# CMOD_A7.net
KiCad netlist of a schematic drawn in Altium Designer
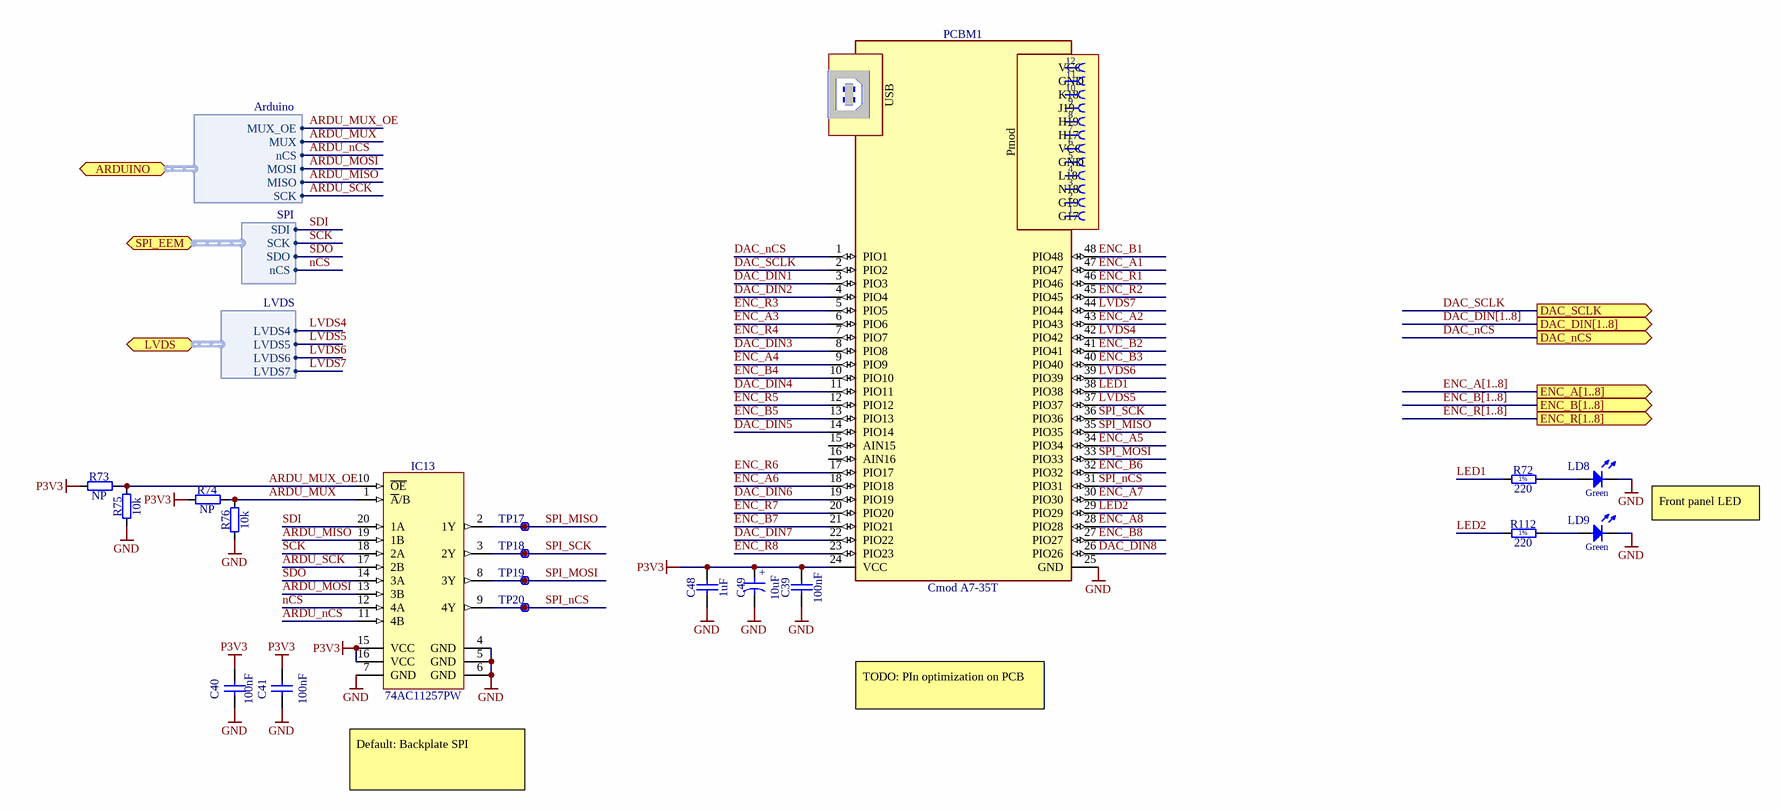
[diagram p0: CMOD_A7.SchDoc]

(export (version "E")
  (design (tool "Eeschema 10.0.6"))
  (components
    (comp (ref "C39")
      (value "100nF")
      (footprint "CAPC1005X55N")
      (description "Non-polarised capacitor")
      (fields
        (field (name "PART NUMBER") "CC0402_100NF_16V_10%_X5R")
        (field (name "VOLTAGE") "16V")
        (field (name "AUTHOR") "CERN DEM JLC")
      )
      (libsource (lib "Capacitors") (part "Capacitor - non polarized"))
    )
    (comp (ref "C40")
      (value "100nF")
      (footprint "CAPC1005X55N")
      (description "Non-polarised capacitor")
      (fields
        (field (name "PART NUMBER") "CC0402_100NF_16V_10%_X5R")
        (field (name "VOLTAGE") "16V")
        (field (name "AUTHOR") "CERN DEM JLC")
      )
      (libsource (lib "Capacitors") (part "Capacitor - non polarized"))
    )
    (comp (ref "C41")
      (value "100nF")
      (footprint "CAPC1005X55N")
      (description "Non-polarised capacitor")
      (fields
        (field (name "PART NUMBER") "CC0402_100NF_16V_10%_X5R")
        (field (name "VOLTAGE") "16V")
        (field (name "AUTHOR") "CERN DEM JLC")
      )
      (libsource (lib "Capacitors") (part "Capacitor - non polarized"))
    )
    (comp (ref "C48")
      (value "1uF")
      (footprint "CAPC1608X87N")
      (description "Non-polarised capacitor")
      (fields
        (field (name "PART NUMBER") "CC0603_1UF_25V_10%_X7R")
        (field (name "VOLTAGE") "25V")
        (field (name "AUTHOR") "CERN DEM JLC")
      )
      (libsource (lib "Capacitors") (part "Capacitor - non polarized"))
    )
    (comp (ref "C49")
      (value "10uF")
      (footprint "CAPMP3216X180N")
      (description "Polarised capacitor")
      (fields
        (field (name "PART NUMBER") "CTE3216-18_10UF_16V_20%_AVX_TCJ")
        (field (name "VOLTAGE") "16V")
        (field (name "AUTHOR") "CERN DEM JLC")
      )
      (libsource (lib "Capacitors") (part "Capacitor - polarized"))
    )
    (comp (ref "IC13")
      (value "74AC11257PW")
      (footprint "SOP65P640X120-20N")
      (description "Quadruple 2-Line to 1-Line Data Selector/Multiplexer With 3-State Outputs")
      (fields (field (name "MANUFACTURER") "TEXAS INSTRUMENTS") (field (name "AUTHOR") "CERN DEM JLC"))
      (libsource (lib "ICs And Semiconductors") (part "7411257"))
    )
    (comp (ref "LD8")
      (value "Green")
      (footprint "LED_DIALIGHT_555-230")
      (description "LED Green 1C 2A")
      (fields
        (field (name "PART NUMBER") "LED_DIALIGHT_555-2301F")
        (field (name "MANUFACTURER") "DIALIGHT")
        (field (name "AUTHOR") "CERN DEM JMW")
      )
      (libsource (lib "ICs And Semiconductors") (part "LED Green 1C 2A"))
    )
    (comp (ref "LD9")
      (value "Green")
      (footprint "LED_DIALIGHT_555-230")
      (description "LED Green 1C 2A")
      (fields
        (field (name "PART NUMBER") "LED_DIALIGHT_555-2301F")
        (field (name "MANUFACTURER") "DIALIGHT")
        (field (name "AUTHOR") "CERN DEM JMW")
      )
      (libsource (lib "ICs And Semiconductors") (part "LED Green 1C 2A"))
    )
    (comp (ref "PCBM1")
      (value "Cmod A7-35T")
      (footprint "PCBM_DIGILENT_CMODA7")
      (description "Breadboardable Artix-7 FPGA Module")
      (fields
        (field (name "PART NUMBER") "PCBM_DIGILENT_CMOD A7-35T")
        (field (name "MANUFACTURER") "DIGILENT")
        (field (name "AUTHOR") "CERN DEM BC")
      )
      (libsource (lib "ICs And Semiconductors") (part "PCBM_DIGILENT_CMODA7"))
    )
    (comp (ref "R72")
      (value "220")
      (footprint "RESC1608X55N")
      (description "Resistor - 1%")
      (fields
        (field (name "PART NUMBER") "R0603_220R_1%_0.1W_100PPM")
        (field (name "POWER") "0.1W")
        (field (name "AUTHOR") "CERN DEM JLC")
      )
      (libsource (lib "") (part "Resistor - 1%_1"))
    )
    (comp (ref "R73")
      (value "NP")
      (footprint "RESC1005X40N")
      (description "Resistor - 1%")
      (fields
        (field (name "PART NUMBER") "R0402_10K_1%_0.0625W_100PPM")
        (field (name "POWER") "0.0625W")
        (field (name "AUTHOR") "CERN DEM JLC")
      )
      (libsource (lib "Resistors") (part "Resistor - 1%"))
    )
    (comp (ref "R74")
      (value "NP")
      (footprint "RESC1005X40N")
      (description "Resistor - 1%")
      (fields
        (field (name "PART NUMBER") "R0402_10K_1%_0.0625W_100PPM")
        (field (name "POWER") "0.0625W")
        (field (name "AUTHOR") "CERN DEM JLC")
      )
      (libsource (lib "Resistors") (part "Resistor - 1%"))
    )
    (comp (ref "R75")
      (value "10k")
      (footprint "RESC1005X40N")
      (description "Resistor - 1%")
      (fields
        (field (name "PART NUMBER") "R0402_10K_1%_0.0625W_100PPM")
        (field (name "POWER") "0.0625W")
        (field (name "AUTHOR") "CERN DEM JLC")
      )
      (libsource (lib "Resistors") (part "Resistor - 1%"))
    )
    (comp (ref "R76")
      (value "10k")
      (footprint "RESC1005X40N")
      (description "Resistor - 1%")
      (fields
        (field (name "PART NUMBER") "R0402_10K_1%_0.0625W_100PPM")
        (field (name "POWER") "0.0625W")
        (field (name "AUTHOR") "CERN DEM JLC")
      )
      (libsource (lib "Resistors") (part "Resistor - 1%"))
    )
    (comp (ref "R112")
      (value "220")
      (footprint "RESC1608X55N")
      (description "Resistor - 1%")
      (fields
        (field (name "PART NUMBER") "R0603_220R_1%_0.1W_100PPM")
        (field (name "POWER") "0.1W")
        (field (name "AUTHOR") "CERN DEM JLC")
      )
      (libsource (lib "") (part "Resistor - 1%_1"))
    )
    (comp (ref "TP17")
      (value "Plated Hole")
      (footprint "c130h60")
      (description "Single Terminal Socket")
      (fields (field (name "PART NUMBER") "PLATED_HOLE0.6_PAD1.3") (field (name "AUTHOR") "CERN DEM MR"))
      (libsource (lib "Eletro-mechanical") (part "Single Terminal Socket"))
    )
    (comp (ref "TP18")
      (value "Plated Hole")
      (footprint "c130h60")
      (description "Single Terminal Socket")
      (fields (field (name "PART NUMBER") "PLATED_HOLE0.6_PAD1.3") (field (name "AUTHOR") "CERN DEM MR"))
      (libsource (lib "Eletro-mechanical") (part "Single Terminal Socket"))
    )
    (comp (ref "TP19")
      (value "Plated Hole")
      (footprint "c130h60")
      (description "Single Terminal Socket")
      (fields (field (name "PART NUMBER") "PLATED_HOLE0.6_PAD1.3") (field (name "AUTHOR") "CERN DEM MR"))
      (libsource (lib "Eletro-mechanical") (part "Single Terminal Socket"))
    )
    (comp (ref "TP20")
      (value "Plated Hole")
      (footprint "c130h60")
      (description "Single Terminal Socket")
      (fields (field (name "PART NUMBER") "PLATED_HOLE0.6_PAD1.3") (field (name "AUTHOR") "CERN DEM MR"))
      (libsource (lib "Eletro-mechanical") (part "Single Terminal Socket"))
    )
  )
  (nets
    (net (code "4") (name "/ARDU_MISO") (class "Default")
      (node (ref "IC13") (pin "19") (pinfunction "1B_19") (pintype "input"))
    )
    (net (code "5") (name "/ARDU_MOSI") (class "Default")
      (node (ref "IC13") (pin "13") (pinfunction "3B_13") (pintype "input"))
    )
    (net (code "6") (name "/ARDU_MUX") (class "Default")
      (node (ref "IC13") (pin "1") (pinfunction "~{A}/B_1") (pintype "input"))
      (node (ref "R74") (pin "2") (pinfunction "2_2") (pintype "passive"))
      (node (ref "R76") (pin "2") (pinfunction "2_2") (pintype "passive"))
    )
    (net (code "7") (name "/ARDU_MUX_OE") (class "Default")
      (node (ref "IC13") (pin "10") (pinfunction "~{OE}_10") (pintype "input"))
      (node (ref "R73") (pin "2") (pinfunction "2_2") (pintype "passive"))
      (node (ref "R75") (pin "2") (pinfunction "2_2") (pintype "passive"))
    )
    (net (code "8") (name "/ARDU_SCK") (class "Default")
      (node (ref "IC13") (pin "17") (pinfunction "2B_17") (pintype "input"))
    )
    (net (code "9") (name "/ARDU_nCS") (class "Default")
      (node (ref "IC13") (pin "11") (pinfunction "4B_11") (pintype "input"))
    )
    (net (code "10") (name "/DAC_DIN1") (class "Default")
      (node (ref "PCBM1") (pin "3") (pinfunction "PIO3_3") (pintype "bidirectional"))
    )
    (net (code "11") (name "/DAC_DIN2") (class "Default")
      (node (ref "PCBM1") (pin "4") (pinfunction "PIO4_4") (pintype "bidirectional"))
    )
    (net (code "12") (name "/DAC_DIN3") (class "Default")
      (node (ref "PCBM1") (pin "8") (pinfunction "PIO8_8") (pintype "bidirectional"))
    )
    (net (code "13") (name "/DAC_DIN4") (class "Default")
      (node (ref "PCBM1") (pin "11") (pinfunction "PIO11_11") (pintype "bidirectional"))
    )
    (net (code "14") (name "/DAC_DIN5") (class "Default")
      (node (ref "PCBM1") (pin "14") (pinfunction "PIO14_14") (pintype "bidirectional"))
    )
    (net (code "15") (name "/DAC_DIN6") (class "Default")
      (node (ref "PCBM1") (pin "19") (pinfunction "PIO19_19") (pintype "bidirectional"))
    )
    (net (code "16") (name "/DAC_DIN7") (class "Default")
      (node (ref "PCBM1") (pin "22") (pinfunction "PIO22_22") (pintype "bidirectional"))
    )
    (net (code "17") (name "/DAC_DIN8") (class "Default")
      (node (ref "PCBM1") (pin "26") (pinfunction "PIO26_26") (pintype "bidirectional"))
    )
    (net (code "19") (name "/DAC_SCLK") (class "Default")
      (node (ref "PCBM1") (pin "2") (pinfunction "PIO2_2") (pintype "bidirectional"))
    )
    (net (code "20") (name "/DAC_nCS") (class "Default")
      (node (ref "PCBM1") (pin "1") (pinfunction "PIO1_1") (pintype "bidirectional"))
    )
    (net (code "21") (name "/ENC_A1") (class "Default")
      (node (ref "PCBM1") (pin "47") (pinfunction "PIO47_47") (pintype "bidirectional"))
    )
    (net (code "22") (name "/ENC_A2") (class "Default")
      (node (ref "PCBM1") (pin "43") (pinfunction "PIO43_43") (pintype "bidirectional"))
    )
    (net (code "23") (name "/ENC_A3") (class "Default")
      (node (ref "PCBM1") (pin "6") (pinfunction "PIO6_6") (pintype "bidirectional"))
    )
    (net (code "24") (name "/ENC_A4") (class "Default")
      (node (ref "PCBM1") (pin "9") (pinfunction "PIO9_9") (pintype "bidirectional"))
    )
    (net (code "25") (name "/ENC_A5") (class "Default")
      (node (ref "PCBM1") (pin "34") (pinfunction "PIO34_34") (pintype "bidirectional"))
    )
    (net (code "26") (name "/ENC_A6") (class "Default")
      (node (ref "PCBM1") (pin "18") (pinfunction "PIO18_18") (pintype "bidirectional"))
    )
    (net (code "27") (name "/ENC_A7") (class "Default")
      (node (ref "PCBM1") (pin "30") (pinfunction "PIO30_30") (pintype "bidirectional"))
    )
    (net (code "28") (name "/ENC_A8") (class "Default")
      (node (ref "PCBM1") (pin "28") (pinfunction "PIO28_28") (pintype "bidirectional"))
    )
    (net (code "30") (name "/ENC_B1") (class "Default")
      (node (ref "PCBM1") (pin "48") (pinfunction "PIO48_48") (pintype "bidirectional"))
    )
    (net (code "31") (name "/ENC_B2") (class "Default")
      (node (ref "PCBM1") (pin "41") (pinfunction "PIO41_41") (pintype "bidirectional"))
    )
    (net (code "32") (name "/ENC_B3") (class "Default")
      (node (ref "PCBM1") (pin "40") (pinfunction "PIO40_40") (pintype "bidirectional"))
    )
    (net (code "33") (name "/ENC_B4") (class "Default")
      (node (ref "PCBM1") (pin "10") (pinfunction "PIO10_10") (pintype "bidirectional"))
    )
    (net (code "34") (name "/ENC_B5") (class "Default")
      (node (ref "PCBM1") (pin "13") (pinfunction "PIO13_13") (pintype "bidirectional"))
    )
    (net (code "35") (name "/ENC_B6") (class "Default")
      (node (ref "PCBM1") (pin "32") (pinfunction "PIO32_32") (pintype "bidirectional"))
    )
    (net (code "36") (name "/ENC_B7") (class "Default")
      (node (ref "PCBM1") (pin "21") (pinfunction "PIO21_21") (pintype "bidirectional"))
    )
    (net (code "37") (name "/ENC_B8") (class "Default")
      (node (ref "PCBM1") (pin "27") (pinfunction "PIO27_27") (pintype "bidirectional"))
    )
    (net (code "39") (name "/ENC_R1") (class "Default")
      (node (ref "PCBM1") (pin "46") (pinfunction "PIO46_46") (pintype "bidirectional"))
    )
    (net (code "40") (name "/ENC_R2") (class "Default")
      (node (ref "PCBM1") (pin "45") (pinfunction "PIO45_45") (pintype "bidirectional"))
    )
    (net (code "41") (name "/ENC_R3") (class "Default")
      (node (ref "PCBM1") (pin "5") (pinfunction "PIO5_5") (pintype "bidirectional"))
    )
    (net (code "42") (name "/ENC_R4") (class "Default")
      (node (ref "PCBM1") (pin "7") (pinfunction "PIO7_7") (pintype "bidirectional"))
    )
    (net (code "43") (name "/ENC_R5") (class "Default")
      (node (ref "PCBM1") (pin "12") (pinfunction "PIO12_12") (pintype "bidirectional"))
    )
    (net (code "44") (name "/ENC_R6") (class "Default")
      (node (ref "PCBM1") (pin "17") (pinfunction "PIO17_17") (pintype "bidirectional"))
    )
    (net (code "45") (name "/ENC_R7") (class "Default")
      (node (ref "PCBM1") (pin "20") (pinfunction "PIO20_20") (pintype "bidirectional"))
    )
    (net (code "46") (name "/ENC_R8") (class "Default")
      (node (ref "PCBM1") (pin "23") (pinfunction "PIO23_23") (pintype "bidirectional"))
    )
    (net (code "48") (name "/LED1") (class "Default")
      (node (ref "PCBM1") (pin "38") (pinfunction "PIO38_38") (pintype "bidirectional"))
      (node (ref "R72") (pin "1") (pinfunction "1_1") (pintype "passive"))
    )
    (net (code "49") (name "/LED2") (class "Default")
      (node (ref "PCBM1") (pin "29") (pinfunction "PIO29_29") (pintype "bidirectional"))
      (node (ref "R112") (pin "1") (pinfunction "1_1") (pintype "passive"))
    )
    (net (code "50") (name "/LVDS4") (class "Default")
      (node (ref "PCBM1") (pin "42") (pinfunction "PIO42_42") (pintype "bidirectional"))
    )
    (net (code "51") (name "/LVDS5") (class "Default")
      (node (ref "PCBM1") (pin "37") (pinfunction "PIO37_37") (pintype "bidirectional"))
    )
    (net (code "52") (name "/LVDS6") (class "Default")
      (node (ref "PCBM1") (pin "39") (pinfunction "PIO39_39") (pintype "bidirectional"))
    )
    (net (code "53") (name "/LVDS7") (class "Default")
      (node (ref "PCBM1") (pin "44") (pinfunction "PIO44_44") (pintype "bidirectional"))
    )
    (net (code "54") (name "/SCK") (class "Default")
      (node (ref "IC13") (pin "18") (pinfunction "2A_18") (pintype "input"))
    )
    (net (code "55") (name "/SDI") (class "Default")
      (node (ref "IC13") (pin "20") (pinfunction "1A_20") (pintype "input"))
    )
    (net (code "56") (name "/SDO") (class "Default")
      (node (ref "IC13") (pin "14") (pinfunction "3A_14") (pintype "input"))
    )
    (net (code "57") (name "/SPI_MISO") (class "Default")
      (node (ref "IC13") (pin "2") (pinfunction "1Y_2") (pintype "output"))
      (node (ref "PCBM1") (pin "35") (pinfunction "PIO35_35") (pintype "bidirectional"))
      (node (ref "TP17") (pin "1") (pinfunction "1_1") (pintype "bidirectional"))
    )
    (net (code "58") (name "/SPI_MOSI") (class "Default")
      (node (ref "IC13") (pin "8") (pinfunction "3Y_8") (pintype "output"))
      (node (ref "PCBM1") (pin "33") (pinfunction "PIO33_33") (pintype "bidirectional"))
      (node (ref "TP19") (pin "1") (pinfunction "1_1") (pintype "bidirectional"))
    )
    (net (code "59") (name "/SPI_SCK") (class "Default")
      (node (ref "IC13") (pin "3") (pinfunction "2Y_3") (pintype "output"))
      (node (ref "PCBM1") (pin "36") (pinfunction "PIO36_36") (pintype "bidirectional"))
      (node (ref "TP18") (pin "1") (pinfunction "1_1") (pintype "bidirectional"))
    )
    (net (code "60") (name "/SPI_nCS") (class "Default")
      (node (ref "IC13") (pin "9") (pinfunction "4Y_9") (pintype "output"))
      (node (ref "PCBM1") (pin "31") (pinfunction "PIO31_31") (pintype "bidirectional"))
      (node (ref "TP20") (pin "1") (pinfunction "1_1") (pintype "bidirectional"))
    )
    (net (code "61") (name "/nCS") (class "Default")
      (node (ref "IC13") (pin "12") (pinfunction "4A_12") (pintype "input"))
    )
    (net (code "65") (name "GND") (class "Default")
      (node (ref "C39") (pin "1") (pinfunction "1_1") (pintype "passive"))
      (node (ref "C40") (pin "1") (pinfunction "1_1") (pintype "passive"))
      (node (ref "C41") (pin "1") (pinfunction "1_1") (pintype "passive"))
      (node (ref "C48") (pin "1") (pinfunction "1_1") (pintype "passive"))
      (node (ref "C49") (pin "2") (pinfunction "2_2") (pintype "passive"))
      (node (ref "IC13") (pin "4") (pinfunction "GND_4") (pintype "power_in"))
      (node (ref "IC13") (pin "5") (pinfunction "GND_5") (pintype "power_in"))
      (node (ref "IC13") (pin "6") (pinfunction "GND_6") (pintype "power_in"))
      (node (ref "IC13") (pin "7") (pinfunction "GND_7") (pintype "power_in"))
      (node (ref "LD8") (pin "1") (pinfunction "C_1") (pintype "passive"))
      (node (ref "LD9") (pin "1") (pinfunction "C_1") (pintype "passive"))
      (node (ref "PCBM1") (pin "25") (pinfunction "GND_25") (pintype "power_in"))
      (node (ref "R75") (pin "1") (pinfunction "1_1") (pintype "passive"))
      (node (ref "R76") (pin "1") (pinfunction "1_1") (pintype "passive"))
    )
    (net (code "66") (name "Net-(LD8-A)") (class "Default")
      (node (ref "LD8") (pin "2") (pinfunction "A_2") (pintype "passive"))
      (node (ref "R72") (pin "2") (pinfunction "2_2") (pintype "passive"))
    )
    (net (code "67") (name "Net-(LD9-A)") (class "Default")
      (node (ref "LD9") (pin "2") (pinfunction "A_2") (pintype "passive"))
      (node (ref "R112") (pin "2") (pinfunction "2_2") (pintype "passive"))
    )
    (net (code "68") (name "P3V3") (class "Default")
      (node (ref "C39") (pin "2") (pinfunction "2_2") (pintype "passive"))
      (node (ref "C40") (pin "2") (pinfunction "2_2") (pintype "passive"))
      (node (ref "C41") (pin "2") (pinfunction "2_2") (pintype "passive"))
      (node (ref "C48") (pin "2") (pinfunction "2_2") (pintype "passive"))
      (node (ref "C49") (pin "1") (pinfunction "1_1") (pintype "passive"))
      (node (ref "IC13") (pin "15") (pinfunction "VCC_15") (pintype "power_in"))
      (node (ref "IC13") (pin "16") (pinfunction "VCC_16") (pintype "power_in"))
      (node (ref "PCBM1") (pin "24") (pinfunction "VCC_24") (pintype "power_in"))
      (node (ref "R73") (pin "1") (pinfunction "1_1") (pintype "passive"))
      (node (ref "R74") (pin "1") (pinfunction "1_1") (pintype "passive"))
    )
    (net (code "69") (name "unconnected-(PCBM1-AIN15-Pad15)") (class "Default")
      (node (ref "PCBM1") (pin "15") (pinfunction "AIN15_15") (pintype "bidirectional"))
    )
    (net (code "70") (name "unconnected-(PCBM1-AIN16-Pad16)") (class "Default")
      (node (ref "PCBM1") (pin "16") (pinfunction "AIN16_16") (pintype "bidirectional"))
    )
  )
)
